# CAN.net
KiCad netlist of a schematic drawn in Altium Designer
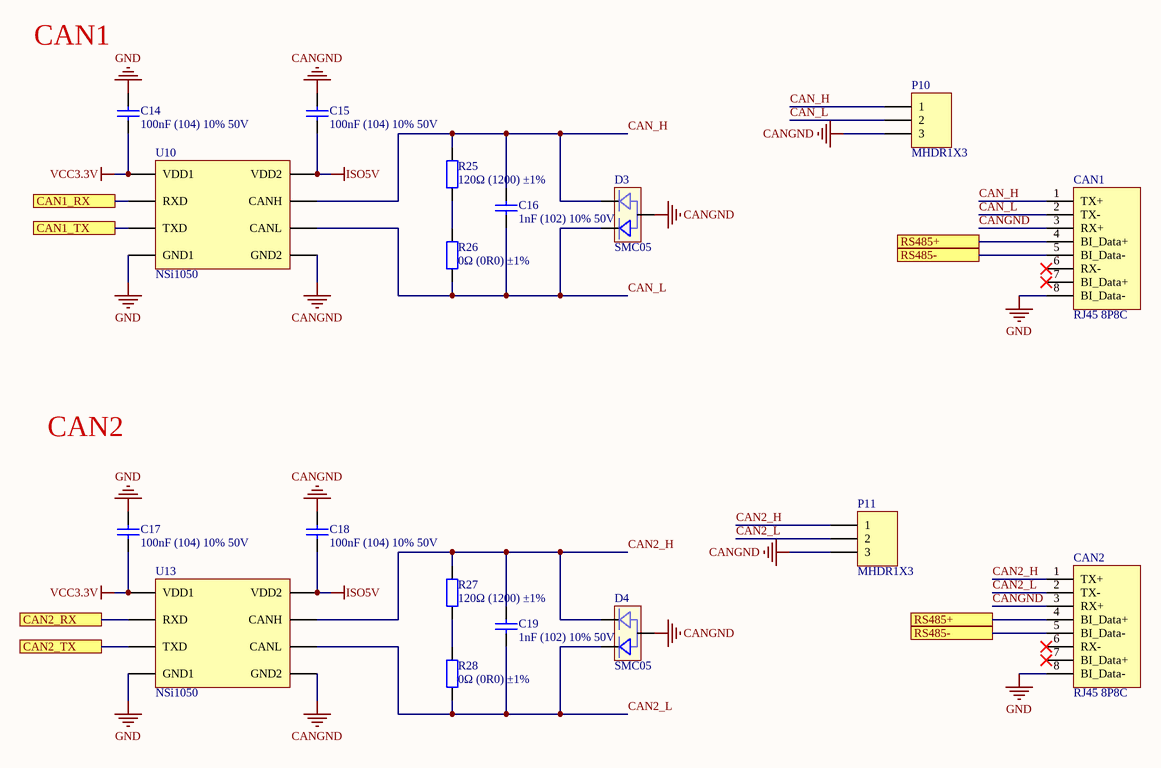
[diagram p0: CAN.SchDoc]

(export (version "E")
  (design (tool "Eeschema 10.0.6"))
  (components
    (comp (ref "C14")
      (value "100nF (104) 10% 50V")
      (footprint "0402_C")
      (description "贴片电容")
      (libsource (lib "Cap") (part "0603 100nF (104) 10% 50V"))
    )
    (comp (ref "C15")
      (value "100nF (104) 10% 50V")
      (footprint "0402_C")
      (description "贴片电容")
      (libsource (lib "Cap") (part "0603 100nF (104) 10% 50V"))
    )
    (comp (ref "C16")
      (value "1nF (102) 10% 50V")
      (footprint "0402_C")
      (description "贴片电容")
      (libsource (lib "Cap") (part "0603 1nF (102) 10% 50V"))
    )
    (comp (ref "C17")
      (value "100nF (104) 10% 50V")
      (footprint "0402_C")
      (description "贴片电容")
      (libsource (lib "Cap") (part "0603 100nF (104) 10% 50V"))
    )
    (comp (ref "C18")
      (value "100nF (104) 10% 50V")
      (footprint "0402_C")
      (description "贴片电容")
      (libsource (lib "Cap") (part "0603 100nF (104) 10% 50V"))
    )
    (comp (ref "C19")
      (value "1nF (102) 10% 50V")
      (footprint "0402_C")
      (description "贴片电容")
      (libsource (lib "Cap") (part "0603 1nF (102) 10% 50V"))
    )
    (comp (ref "CAN1")
      (value "RJ45 8P8C")
      (footprint "RJ45-8P8C")
      (description "以太网接口")
      (libsource (lib "Library") (part "RJ45-8P8C"))
    )
    (comp (ref "CAN2")
      (value "RJ45 8P8C")
      (footprint "RJ45-8P8C")
      (description "以太网接口")
      (libsource (lib "Library") (part "RJ45-8P8C"))
    )
    (comp (ref "D3")
      (value "SMC05")
      (footprint "SOT-23")
      (description "瞬态抑制二极管")
      (libsource (lib "Library") (part "Diode-TVS"))
    )
    (comp (ref "D4")
      (value "SMC05")
      (footprint "SOT-23")
      (description "瞬态抑制二极管")
      (libsource (lib "Library") (part "Diode-TVS"))
    )
    (comp (ref "P10")
      (value "MHDR1X3")
      (footprint "SH1.0-3P-L")
      (description "Header, 3-Pin")
      (fields (field (name "PUBLISHER") "Altium Limited"))
      (libsource (lib "Miscellaneous Connectors") (part "MHDR1X3"))
    )
    (comp (ref "P11")
      (value "MHDR1X3")
      (footprint "SH1.0-3P-L")
      (description "Header, 3-Pin")
      (fields (field (name "PUBLISHER") "Altium Limited"))
      (libsource (lib "Miscellaneous Connectors") (part "MHDR1X3"))
    )
    (comp (ref "R25")
      (value "120Ω (1200) ±1%")
      (footprint "0402_R")
      (description "贴片电阻")
      (libsource (lib "RES") (part "0603 120Ω (1200) 1%"))
    )
    (comp (ref "R26")
      (value "0Ω (0R0) ±1%")
      (footprint "0402_R")
      (description "贴片电阻")
      (libsource (lib "RES") (part "0603 0Ω (0R0) 1%"))
    )
    (comp (ref "R27")
      (value "120Ω (1200) ±1%")
      (footprint "0402_R")
      (description "贴片电阻")
      (libsource (lib "RES") (part "0603 120Ω (1200) 1%"))
    )
    (comp (ref "R28")
      (value "0Ω (0R0) ±1%")
      (footprint "0402_R")
      (description "贴片电阻")
      (libsource (lib "RES") (part "0603 0Ω (0R0) 1%"))
    )
    (comp (ref "U10")
      (value "NSi1050")
      (footprint "SOP8-W2.54")
      (description "CAN隔离收发器")
      (libsource (lib "Library") (part "NSi1050"))
    )
    (comp (ref "U13")
      (value "NSi1050")
      (footprint "SOP8-W2.54")
      (description "CAN隔离收发器")
      (libsource (lib "Library") (part "NSi1050"))
    )
  )
  (nets
    (net (code "1") (name "/CAN1_RX") (class "Default")
      (node (ref "U10") (pin "2") (pinfunction "RXD_2") (pintype "passive"))
    )
    (net (code "2") (name "/CAN1_TX") (class "Default")
      (node (ref "U10") (pin "3") (pinfunction "TXD_3") (pintype "passive"))
    )
    (net (code "3") (name "/CAN2_H") (class "Default")
      (node (ref "C19") (pin "2") (pinfunction "2_2") (pintype "passive"))
      (node (ref "CAN2") (pin "1") (pinfunction "TX+_1") (pintype "passive"))
      (node (ref "D4") (pin "1") (pinfunction "1_1") (pintype "passive"))
      (node (ref "P11") (pin "1") (pinfunction "1_1") (pintype "passive"))
      (node (ref "R27") (pin "2") (pinfunction "2_2") (pintype "passive"))
      (node (ref "U13") (pin "7") (pinfunction "CANH_7") (pintype "passive"))
    )
    (net (code "4") (name "/CAN2_L") (class "Default")
      (node (ref "C19") (pin "1") (pinfunction "1_1") (pintype "passive"))
      (node (ref "CAN2") (pin "2") (pinfunction "TX-_2") (pintype "passive"))
      (node (ref "D4") (pin "2") (pinfunction "2_2") (pintype "passive"))
      (node (ref "P11") (pin "2") (pinfunction "2_2") (pintype "passive"))
      (node (ref "R28") (pin "1") (pinfunction "1_1") (pintype "passive"))
      (node (ref "U13") (pin "6") (pinfunction "CANL_6") (pintype "passive"))
    )
    (net (code "5") (name "/CAN2_RX") (class "Default")
      (node (ref "U13") (pin "2") (pinfunction "RXD_2") (pintype "passive"))
    )
    (net (code "6") (name "/CAN2_TX") (class "Default")
      (node (ref "U13") (pin "3") (pinfunction "TXD_3") (pintype "passive"))
    )
    (net (code "7") (name "/CAN_H") (class "Default")
      (node (ref "C16") (pin "2") (pinfunction "2_2") (pintype "passive"))
      (node (ref "CAN1") (pin "1") (pinfunction "TX+_1") (pintype "passive"))
      (node (ref "D3") (pin "1") (pinfunction "1_1") (pintype "passive"))
      (node (ref "P10") (pin "1") (pinfunction "1_1") (pintype "passive"))
      (node (ref "R25") (pin "2") (pinfunction "2_2") (pintype "passive"))
      (node (ref "U10") (pin "7") (pinfunction "CANH_7") (pintype "passive"))
    )
    (net (code "8") (name "/CAN_L") (class "Default")
      (node (ref "C16") (pin "1") (pinfunction "1_1") (pintype "passive"))
      (node (ref "CAN1") (pin "2") (pinfunction "TX-_2") (pintype "passive"))
      (node (ref "D3") (pin "2") (pinfunction "2_2") (pintype "passive"))
      (node (ref "P10") (pin "2") (pinfunction "2_2") (pintype "passive"))
      (node (ref "R26") (pin "1") (pinfunction "1_1") (pintype "passive"))
      (node (ref "U10") (pin "6") (pinfunction "CANL_6") (pintype "passive"))
    )
    (net (code "9") (name "/RS485+") (class "Default")
      (node (ref "CAN1") (pin "4") (pinfunction "BI_Data+_4") (pintype "passive"))
      (node (ref "CAN2") (pin "4") (pinfunction "BI_Data+_4") (pintype "passive"))
    )
    (net (code "10") (name "/RS485-") (class "Default")
      (node (ref "CAN1") (pin "5") (pinfunction "BI_Data-_5") (pintype "passive"))
      (node (ref "CAN2") (pin "5") (pinfunction "BI_Data-_5") (pintype "passive"))
    )
    (net (code "11") (name "CANGND") (class "Default")
      (node (ref "C15") (pin "1") (pinfunction "1_1") (pintype "passive"))
      (node (ref "C18") (pin "1") (pinfunction "1_1") (pintype "passive"))
      (node (ref "CAN1") (pin "3") (pinfunction "RX+_3") (pintype "passive"))
      (node (ref "CAN2") (pin "3") (pinfunction "RX+_3") (pintype "passive"))
      (node (ref "D3") (pin "3") (pinfunction "3_3") (pintype "passive"))
      (node (ref "D4") (pin "3") (pinfunction "3_3") (pintype "passive"))
      (node (ref "P10") (pin "3") (pinfunction "3_3") (pintype "passive"))
      (node (ref "P11") (pin "3") (pinfunction "3_3") (pintype "passive"))
      (node (ref "U10") (pin "5") (pinfunction "GND2_5") (pintype "passive"))
      (node (ref "U13") (pin "5") (pinfunction "GND2_5") (pintype "passive"))
    )
    (net (code "12") (name "GND") (class "Default")
      (node (ref "C14") (pin "1") (pinfunction "1_1") (pintype "passive"))
      (node (ref "C17") (pin "1") (pinfunction "1_1") (pintype "passive"))
      (node (ref "CAN1") (pin "8") (pinfunction "BI_Data-_8") (pintype "passive"))
      (node (ref "CAN2") (pin "8") (pinfunction "BI_Data-_8") (pintype "passive"))
      (node (ref "U10") (pin "4") (pinfunction "GND1_4") (pintype "passive"))
      (node (ref "U13") (pin "4") (pinfunction "GND1_4") (pintype "passive"))
    )
    (net (code "13") (name "ISO5V") (class "Default")
      (node (ref "C15") (pin "2") (pinfunction "2_2") (pintype "passive"))
      (node (ref "C18") (pin "2") (pinfunction "2_2") (pintype "passive"))
      (node (ref "U10") (pin "8") (pinfunction "VDD2_8") (pintype "passive"))
      (node (ref "U13") (pin "8") (pinfunction "VDD2_8") (pintype "passive"))
    )
    (net (code "14") (name "Net-(R25-Pad1)") (class "Default")
      (node (ref "R25") (pin "1") (pinfunction "1_1") (pintype "passive"))
      (node (ref "R26") (pin "2") (pinfunction "2_2") (pintype "passive"))
    )
    (net (code "15") (name "Net-(R27-Pad1)") (class "Default")
      (node (ref "R27") (pin "1") (pinfunction "1_1") (pintype "passive"))
      (node (ref "R28") (pin "2") (pinfunction "2_2") (pintype "passive"))
    )
    (net (code "16") (name "VCC3.3V") (class "Default")
      (node (ref "C14") (pin "2") (pinfunction "2_2") (pintype "passive"))
      (node (ref "C17") (pin "2") (pinfunction "2_2") (pintype "passive"))
      (node (ref "U10") (pin "1") (pinfunction "VDD1_1") (pintype "passive"))
      (node (ref "U13") (pin "1") (pinfunction "VDD1_1") (pintype "passive"))
    )
    (net (code "17") (name "unconnected-(CAN1-BI_Data+-Pad7)") (class "Default")
      (node (ref "CAN1") (pin "7") (pinfunction "BI_Data+_7") (pintype "passive+no_connect"))
    )
    (net (code "18") (name "unconnected-(CAN1-RX--Pad6)") (class "Default")
      (node (ref "CAN1") (pin "6") (pinfunction "RX-_6") (pintype "passive+no_connect"))
    )
    (net (code "19") (name "unconnected-(CAN2-BI_Data+-Pad7)") (class "Default")
      (node (ref "CAN2") (pin "7") (pinfunction "BI_Data+_7") (pintype "passive+no_connect"))
    )
    (net (code "20") (name "unconnected-(CAN2-RX--Pad6)") (class "Default")
      (node (ref "CAN2") (pin "6") (pinfunction "RX-_6") (pintype "passive+no_connect"))
    )
  )
)
